# transistors.net
KiCad netlist of a schematic drawn in EAGLE
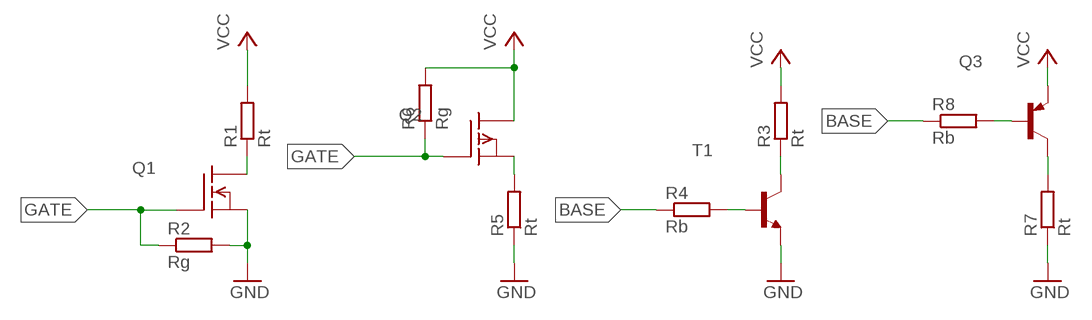
[diagram p0: schematic, sheet 1]

(export (version "E")
  (design (tool "Eeschema 10.0.6"))
  (components
    (comp (ref "Q1")
      (value "BSS97")
      (footprint "eagle-import:TO202")
      (libsource (lib "eagle-import") (part "BSS97"))
    )
    (comp (ref "Q2")
      (value "BSS92")
      (footprint "eagle-import:TO92")
      (libsource (lib "eagle-import") (part "BSS92"))
    )
    (comp (ref "Q3")
      (value "2N3576")
      (footprint "eagle-import:TO18")
      (libsource (lib "eagle-import") (part "2N3576"))
    )
    (comp (ref "R1")
      (value "Rt")
      (footprint "eagle-import:0207_15")
      (libsource (lib "eagle-import") (part "R-EU_0207/15"))
    )
    (comp (ref "R2")
      (value "Rg")
      (footprint "eagle-import:0207_15")
      (libsource (lib "eagle-import") (part "R-EU_0207/15"))
    )
    (comp (ref "R3")
      (value "Rt")
      (footprint "eagle-import:0207_15")
      (libsource (lib "eagle-import") (part "R-EU_0207/15"))
    )
    (comp (ref "R4")
      (value "Rb")
      (footprint "eagle-import:0207_15")
      (libsource (lib "eagle-import") (part "R-EU_0207/15"))
    )
    (comp (ref "R5")
      (value "Rt")
      (footprint "eagle-import:0207_15")
      (libsource (lib "eagle-import") (part "R-EU_0207/15"))
    )
    (comp (ref "R6")
      (value "Rg")
      (footprint "eagle-import:0207_15")
      (libsource (lib "eagle-import") (part "R-EU_0207/15"))
    )
    (comp (ref "R7")
      (value "Rt")
      (footprint "eagle-import:0207_15")
      (libsource (lib "eagle-import") (part "R-EU_0207/15"))
    )
    (comp (ref "R8")
      (value "Rb")
      (footprint "eagle-import:0207_15")
      (libsource (lib "eagle-import") (part "R-EU_0207/15"))
    )
    (comp (ref "T1")
      (value "2N2219")
      (footprint "eagle-import:TO5")
      (libsource (lib "eagle-import") (part "2N2219"))
    )
  )
  (nets
    (net (code "1") (name "BASE") (class "Default")
      (node (ref "R4") (pin "1") (pinfunction "1_1") (pintype "passive"))
      (node (ref "R8") (pin "1") (pinfunction "1_1") (pintype "passive"))
    )
    (net (code "2") (name "GATE") (class "Default")
      (node (ref "Q1") (pin "3") (pinfunction "G_3") (pintype "passive"))
      (node (ref "Q2") (pin "1") (pinfunction "G_1") (pintype "passive"))
      (node (ref "R2") (pin "1") (pinfunction "1_1") (pintype "passive"))
      (node (ref "R6") (pin "1") (pinfunction "1_1") (pintype "passive"))
    )
    (net (code "3") (name "GND") (class "Default")
      (node (ref "Q1") (pin "1") (pinfunction "S_1") (pintype "passive"))
      (node (ref "R2") (pin "2") (pinfunction "2_2") (pintype "passive"))
      (node (ref "R5") (pin "1") (pinfunction "1_1") (pintype "passive"))
      (node (ref "R7") (pin "1") (pinfunction "1_1") (pintype "passive"))
      (node (ref "T1") (pin "1") (pinfunction "E_1") (pintype "passive"))
    )
    (net (code "4") (name "Net-(Q1-D)") (class "Default")
      (node (ref "Q1") (pin "2") (pinfunction "D_2") (pintype "passive"))
      (node (ref "R1") (pin "1") (pinfunction "1_1") (pintype "passive"))
    )
    (net (code "5") (name "Net-(Q2-S)") (class "Default")
      (node (ref "Q2") (pin "3") (pinfunction "S_3") (pintype "passive"))
      (node (ref "R5") (pin "2") (pinfunction "2_2") (pintype "passive"))
    )
    (net (code "6") (name "Net-(Q3-B)") (class "Default")
      (node (ref "Q3") (pin "2") (pinfunction "B_2") (pintype "passive"))
      (node (ref "R8") (pin "2") (pinfunction "2_2") (pintype "passive"))
    )
    (net (code "7") (name "Net-(Q3-C)") (class "Default")
      (node (ref "Q3") (pin "3") (pinfunction "C_3") (pintype "passive"))
      (node (ref "R7") (pin "2") (pinfunction "2_2") (pintype "passive"))
    )
    (net (code "8") (name "Net-(T1-B)") (class "Default")
      (node (ref "R4") (pin "2") (pinfunction "2_2") (pintype "passive"))
      (node (ref "T1") (pin "2") (pinfunction "B_2") (pintype "passive"))
    )
    (net (code "9") (name "Net-(T1-C)") (class "Default")
      (node (ref "R3") (pin "1") (pinfunction "1_1") (pintype "passive"))
      (node (ref "T1") (pin "3") (pinfunction "C_3") (pintype "passive"))
    )
    (net (code "10") (name "VCC") (class "Default")
      (node (ref "Q2") (pin "2") (pinfunction "D_2") (pintype "passive"))
      (node (ref "Q3") (pin "1") (pinfunction "E_1") (pintype "passive"))
      (node (ref "R1") (pin "2") (pinfunction "2_2") (pintype "passive"))
      (node (ref "R3") (pin "2") (pinfunction "2_2") (pintype "passive"))
      (node (ref "R6") (pin "2") (pinfunction "2_2") (pintype "passive"))
    )
  )
)
